# untitled.net
KiCad netlist of a schematic drawn in EAGLE
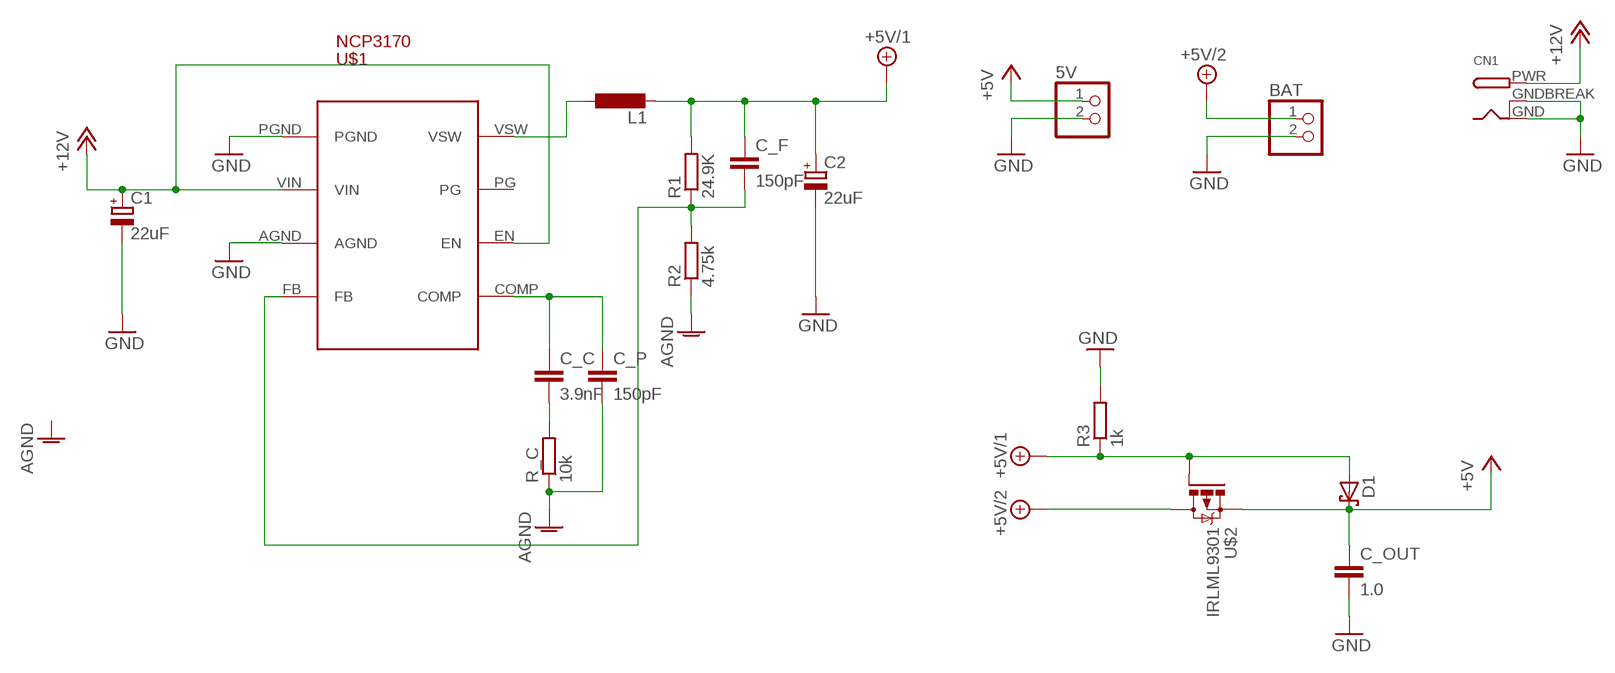
[diagram p0: schematic, sheet 1]

(export (version "E")
  (design (tool "Eeschema 10.0.6"))
  (components
    (comp (ref "5V")
      (value "PINHD-1X2")
      (footprint "eagle-import:1X02")
      (libsource (lib "eagle-import") (part "PINHD-1X2"))
    )
    (comp (ref "BAT")
      (value "PINHD-1X2")
      (footprint "eagle-import:1X02")
      (libsource (lib "eagle-import") (part "PINHD-1X2"))
    )
    (comp (ref "C1")
      (value "22uF")
      (footprint "eagle-import:E2-5")
      (libsource (lib "eagle-import") (part "CPOL-EUE2-5"))
    )
    (comp (ref "C2")
      (value "22uF")
      (footprint "eagle-import:E2-5")
      (libsource (lib "eagle-import") (part "CPOL-EUE2-5"))
    )
    (comp (ref "CN1")
      (value "DCBARRELPTH")
      (footprint "eagle-import:DCJACK_2MM_PTH")
      (libsource (lib "eagle-import") (part "DCBARRELPTH"))
    )
    (comp (ref "C_C")
      (value "3.9nF")
      (footprint "eagle-import:C0805K")
      (libsource (lib "eagle-import") (part "C-EUC0805K"))
    )
    (comp (ref "C_F")
      (value "150pF")
      (footprint "eagle-import:C0805K")
      (libsource (lib "eagle-import") (part "C-EUC0805K"))
    )
    (comp (ref "C_OUT")
      (value "1.0")
      (footprint "eagle-import:C0805K")
      (libsource (lib "eagle-import") (part "C-EUC0805K"))
    )
    (comp (ref "C_P")
      (value "150pF")
      (footprint "eagle-import:C0805K")
      (libsource (lib "eagle-import") (part "C-EUC0805K"))
    )
    (comp (ref "D1")
      (value "SCHOTTKY-DIODESMD")
      (footprint "eagle-import:SMB")
      (libsource (lib "eagle-import") (part "SCHOTTKY-DIODESMD"))
    )
    (comp (ref "L1")
      (value "L-EU0207/7")
      (footprint "eagle-import:0207_7")
      (libsource (lib "eagle-import") (part "L-EU0207/7"))
    )
    (comp (ref "R1")
      (value "24.9K")
      (footprint "eagle-import:R0805")
      (libsource (lib "eagle-import") (part "R-EU_R0805"))
    )
    (comp (ref "R2")
      (value "4.75k")
      (footprint "eagle-import:R0805")
      (libsource (lib "eagle-import") (part "R-EU_R0805"))
    )
    (comp (ref "R3")
      (value "1k")
      (footprint "eagle-import:R0805")
      (libsource (lib "eagle-import") (part "R-EU_R0805"))
    )
    (comp (ref "R_C")
      (value "10k")
      (footprint "eagle-import:R0805")
      (libsource (lib "eagle-import") (part "R-EU_R0805"))
    )
    (comp (ref "U$1")
      (value "NCP3170")
      (footprint "eagle-import:SOIC8")
      (libsource (lib "eagle-import") (part "NCP3170"))
    )
    (comp (ref "U$2")
      (value "IRLML9301")
      (footprint "eagle-import:SOT23")
      (libsource (lib "eagle-import") (part "IRLML9301"))
    )
  )
  (nets
    (net (code "1") (name "+5V") (class "Default")
      (node (ref "5V") (pin "1") (pinfunction "1_1") (pintype "passive"))
      (node (ref "C_OUT") (pin "1") (pinfunction "1_1") (pintype "passive"))
      (node (ref "D1") (pin "C") (pinfunction "C_C") (pintype "passive"))
      (node (ref "U$2") (pin "S") (pinfunction "S_S") (pintype "passive"))
    )
    (net (code "2") (name "+5V{slash}1") (class "Default")
      (node (ref "C2") (pin "+") (pinfunction "+_+") (pintype "passive"))
      (node (ref "C_F") (pin "1") (pinfunction "1_1") (pintype "passive"))
      (node (ref "D1") (pin "A") (pinfunction "A_A") (pintype "passive"))
      (node (ref "L1") (pin "2") (pinfunction "2_2") (pintype "passive"))
      (node (ref "R1") (pin "2") (pinfunction "2_2") (pintype "passive"))
      (node (ref "R3") (pin "1") (pinfunction "1_1") (pintype "passive"))
      (node (ref "U$2") (pin "G") (pinfunction "G_G") (pintype "passive"))
    )
    (net (code "3") (name "+5V{slash}2") (class "Default")
      (node (ref "BAT") (pin "1") (pinfunction "1_1") (pintype "passive"))
      (node (ref "U$2") (pin "D") (pinfunction "D_D") (pintype "passive"))
    )
    (net (code "4") (name "+12V") (class "Default")
      (node (ref "C1") (pin "+") (pinfunction "+_+") (pintype "passive"))
      (node (ref "CN1") (pin "PWR") (pinfunction "PWR_PWR") (pintype "power_in"))
      (node (ref "U$1") (pin "EN") (pinfunction "EN_EN") (pintype "input"))
      (node (ref "U$1") (pin "VIN") (pinfunction "VIN_VIN") (pintype "input"))
    )
    (net (code "5") (name "AGND") (class "Default")
      (node (ref "C_P") (pin "2") (pinfunction "2_2") (pintype "passive"))
      (node (ref "R2") (pin "1") (pinfunction "1_1") (pintype "passive"))
      (node (ref "R_C") (pin "1") (pinfunction "1_1") (pintype "passive"))
    )
    (net (code "6") (name "GND") (class "Default")
      (node (ref "5V") (pin "2") (pinfunction "2_2") (pintype "passive"))
      (node (ref "BAT") (pin "2") (pinfunction "2_2") (pintype "passive"))
      (node (ref "C1") (pin "-") (pinfunction "-_-") (pintype "passive"))
      (node (ref "C2") (pin "-") (pinfunction "-_-") (pintype "passive"))
      (node (ref "CN1") (pin "GND") (pinfunction "GND_GND") (pintype "power_in"))
      (node (ref "CN1") (pin "GNDBREAK") (pinfunction "GNDBREAK_GNDBREAK") (pintype "power_in"))
      (node (ref "C_OUT") (pin "2") (pinfunction "2_2") (pintype "passive"))
      (node (ref "R3") (pin "2") (pinfunction "2_2") (pintype "passive"))
      (node (ref "U$1") (pin "AGND") (pinfunction "AGND_AGND") (pintype "input"))
      (node (ref "U$1") (pin "PGND") (pinfunction "PGND_PGND") (pintype "input"))
    )
    (net (code "7") (name "Net-(C_C-Pad1)") (class "Default")
      (node (ref "C_C") (pin "1") (pinfunction "1_1") (pintype "passive"))
      (node (ref "C_P") (pin "1") (pinfunction "1_1") (pintype "passive"))
      (node (ref "U$1") (pin "COMP") (pinfunction "COMP_COMP") (pintype "input"))
    )
    (net (code "8") (name "Net-(C_C-Pad2)") (class "Default")
      (node (ref "C_C") (pin "2") (pinfunction "2_2") (pintype "passive"))
      (node (ref "R_C") (pin "2") (pinfunction "2_2") (pintype "passive"))
    )
    (net (code "9") (name "Net-(C_F-Pad2)") (class "Default")
      (node (ref "C_F") (pin "2") (pinfunction "2_2") (pintype "passive"))
      (node (ref "R1") (pin "1") (pinfunction "1_1") (pintype "passive"))
      (node (ref "R2") (pin "2") (pinfunction "2_2") (pintype "passive"))
      (node (ref "U$1") (pin "FB") (pinfunction "FB_FB") (pintype "input"))
    )
    (net (code "10") (name "Net-(L1-Pad1)") (class "Default")
      (node (ref "L1") (pin "1") (pinfunction "1_1") (pintype "passive"))
      (node (ref "U$1") (pin "VSW") (pinfunction "VSW_VSW") (pintype "output"))
    )
    (net (code "11") (name "unconnected-(U$1-PadPG)") (class "Default")
      (node (ref "U$1") (pin "PG") (pinfunction "PG_PG") (pintype "input"))
    )
  )
)
